# ASBB_Sonar.net
KiCad netlist of a schematic drawn in Altium Designer
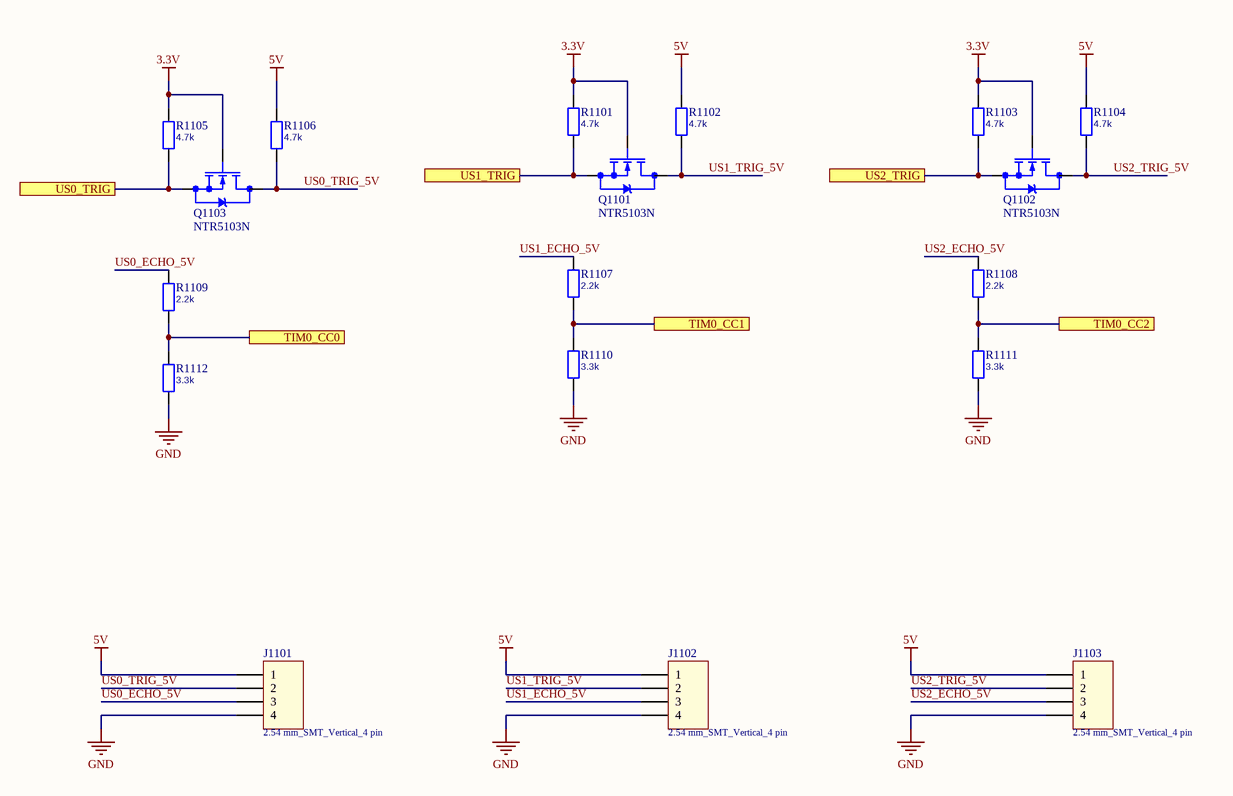
[diagram p0: ASBB_Sonar.SchDoc]

(export (version "E")
  (design (tool "Eeschema 10.0.6"))
  (components
    (comp (ref "J1101")
      (value "2.54 mm_SMT_Vertical_4 pin")
      (footprint "61000411921")
      (description "Socket Header WR-PHD, Pitch 2.54 mm, SMT, Vertical, single row, 4 pin")
      (fields (field (name "PART NUMBER") "61000411921") (field (name "PUBLISHER") "Wurth Elektronik"))
      (libsource (lib "6220xx21821 (rev18a)") (part "61000411921"))
    )
    (comp (ref "J1102")
      (value "2.54 mm_SMT_Vertical_4 pin")
      (footprint "61000411921")
      (description "Socket Header WR-PHD, Pitch 2.54 mm, SMT, Vertical, single row, 4 pin")
      (fields (field (name "PART NUMBER") "61000411921") (field (name "PUBLISHER") "Wurth Elektronik"))
      (libsource (lib "6220xx21821 (rev18a)") (part "61000411921"))
    )
    (comp (ref "J1103")
      (value "2.54 mm_SMT_Vertical_4 pin")
      (footprint "61000411921")
      (description "Socket Header WR-PHD, Pitch 2.54 mm, SMT, Vertical, single row, 4 pin")
      (fields (field (name "PART NUMBER") "61000411921") (field (name "PUBLISHER") "Wurth Elektronik"))
      (libsource (lib "6220xx21821 (rev18a)") (part "61000411921"))
    )
    (comp (ref "Q1101")
      (value "NTR5103N")
      (footprint "FZI:SOT23")
      (description "N-Channel MOSFET SOT23")
      (fields (field (name "PARTNUMBER") "?"))
      (libsource (lib "FZI") (part "NMOS SOT23"))
    )
    (comp (ref "Q1102")
      (value "NTR5103N")
      (footprint "FZI:SOT23")
      (description "N-Channel MOSFET SOT23")
      (fields (field (name "PARTNUMBER") "?"))
      (libsource (lib "FZI") (part "NMOS SOT23"))
    )
    (comp (ref "Q1103")
      (value "NTR5103N")
      (footprint "FZI:SOT23")
      (description "N-Channel MOSFET SOT23")
      (fields (field (name "PARTNUMBER") "?"))
      (libsource (lib "FZI") (part "NMOS SOT23"))
    )
    (comp (ref "R1101")
      (value "4.7k")
      (footprint "0603")
      (description "Resistor")
      (fields (field (name "PARTNUMBER") "?"))
      (libsource (lib "FZI") (part "Resistor"))
    )
    (comp (ref "R1102")
      (value "4.7k")
      (footprint "0603")
      (description "Resistor")
      (fields (field (name "PARTNUMBER") "?"))
      (libsource (lib "FZI") (part "Resistor"))
    )
    (comp (ref "R1103")
      (value "4.7k")
      (footprint "0603")
      (description "Resistor")
      (fields (field (name "PARTNUMBER") "?"))
      (libsource (lib "FZI") (part "Resistor"))
    )
    (comp (ref "R1104")
      (value "4.7k")
      (footprint "0603")
      (description "Resistor")
      (fields (field (name "PARTNUMBER") "?"))
      (libsource (lib "FZI") (part "Resistor"))
    )
    (comp (ref "R1105")
      (value "4.7k")
      (footprint "0603")
      (description "Resistor")
      (fields (field (name "PARTNUMBER") "?"))
      (libsource (lib "FZI") (part "Resistor"))
    )
    (comp (ref "R1106")
      (value "4.7k")
      (footprint "0603")
      (description "Resistor")
      (fields (field (name "PARTNUMBER") "?"))
      (libsource (lib "FZI") (part "Resistor"))
    )
    (comp (ref "R1107")
      (value "2.2k")
      (footprint "0603")
      (description "Resistor")
      (fields (field (name "PARTNUMBER") "?"))
      (libsource (lib "FZI") (part "Resistor"))
    )
    (comp (ref "R1108")
      (value "2.2k")
      (footprint "0603")
      (description "Resistor")
      (fields (field (name "PARTNUMBER") "?"))
      (libsource (lib "FZI") (part "Resistor"))
    )
    (comp (ref "R1109")
      (value "2.2k")
      (footprint "0603")
      (description "Resistor")
      (fields (field (name "PARTNUMBER") "?"))
      (libsource (lib "FZI") (part "Resistor"))
    )
    (comp (ref "R1110")
      (value "3.3k")
      (footprint "0603")
      (description "Resistor")
      (fields (field (name "PARTNUMBER") "?"))
      (libsource (lib "FZI") (part "Resistor"))
    )
    (comp (ref "R1111")
      (value "3.3k")
      (footprint "0603")
      (description "Resistor")
      (fields (field (name "PARTNUMBER") "?"))
      (libsource (lib "FZI") (part "Resistor"))
    )
    (comp (ref "R1112")
      (value "3.3k")
      (footprint "0603")
      (description "Resistor")
      (fields (field (name "PARTNUMBER") "?"))
      (libsource (lib "FZI") (part "Resistor"))
    )
  )
  (nets
    (net (code "1") (name "/TIM0_CC0") (class "Default")
      (node (ref "R1109") (pin "1") (pinfunction "1_1") (pintype "passive"))
      (node (ref "R1112") (pin "2") (pinfunction "2_2") (pintype "passive"))
    )
    (net (code "2") (name "/TIM0_CC1") (class "Default")
      (node (ref "R1107") (pin "1") (pinfunction "1_1") (pintype "passive"))
      (node (ref "R1110") (pin "2") (pinfunction "2_2") (pintype "passive"))
    )
    (net (code "3") (name "/TIM0_CC2") (class "Default")
      (node (ref "R1108") (pin "1") (pinfunction "1_1") (pintype "passive"))
      (node (ref "R1111") (pin "2") (pinfunction "2_2") (pintype "passive"))
    )
    (net (code "4") (name "/US0_ECHO_5V") (class "Default")
      (node (ref "J1101") (pin "3") (pinfunction "3_3") (pintype "passive"))
      (node (ref "R1109") (pin "2") (pinfunction "2_2") (pintype "passive"))
    )
    (net (code "5") (name "/US0_TRIG") (class "Default")
      (node (ref "Q1103") (pin "2") (pinfunction "S_2") (pintype "passive"))
      (node (ref "R1105") (pin "1") (pinfunction "1_1") (pintype "passive"))
    )
    (net (code "6") (name "/US0_TRIG_5V") (class "Default")
      (node (ref "J1101") (pin "2") (pinfunction "2_2") (pintype "passive"))
      (node (ref "Q1103") (pin "3") (pinfunction "D_3") (pintype "passive"))
      (node (ref "R1106") (pin "1") (pinfunction "1_1") (pintype "passive"))
    )
    (net (code "7") (name "/US1_ECHO_5V") (class "Default")
      (node (ref "J1102") (pin "3") (pinfunction "3_3") (pintype "passive"))
      (node (ref "R1107") (pin "2") (pinfunction "2_2") (pintype "passive"))
    )
    (net (code "8") (name "/US1_TRIG") (class "Default")
      (node (ref "Q1101") (pin "2") (pinfunction "S_2") (pintype "passive"))
      (node (ref "R1101") (pin "1") (pinfunction "1_1") (pintype "passive"))
    )
    (net (code "9") (name "/US1_TRIG_5V") (class "Default")
      (node (ref "J1102") (pin "2") (pinfunction "2_2") (pintype "passive"))
      (node (ref "Q1101") (pin "3") (pinfunction "D_3") (pintype "passive"))
      (node (ref "R1102") (pin "1") (pinfunction "1_1") (pintype "passive"))
    )
    (net (code "10") (name "/US2_ECHO_5V") (class "Default")
      (node (ref "J1103") (pin "3") (pinfunction "3_3") (pintype "passive"))
      (node (ref "R1108") (pin "2") (pinfunction "2_2") (pintype "passive"))
    )
    (net (code "11") (name "/US2_TRIG") (class "Default")
      (node (ref "Q1102") (pin "2") (pinfunction "S_2") (pintype "passive"))
      (node (ref "R1103") (pin "1") (pinfunction "1_1") (pintype "passive"))
    )
    (net (code "12") (name "/US2_TRIG_5V") (class "Default")
      (node (ref "J1103") (pin "2") (pinfunction "2_2") (pintype "passive"))
      (node (ref "Q1102") (pin "3") (pinfunction "D_3") (pintype "passive"))
      (node (ref "R1104") (pin "1") (pinfunction "1_1") (pintype "passive"))
    )
    (net (code "13") (name "3.3V") (class "Default")
      (node (ref "Q1101") (pin "1") (pinfunction "G_1") (pintype "passive"))
      (node (ref "Q1102") (pin "1") (pinfunction "G_1") (pintype "passive"))
      (node (ref "Q1103") (pin "1") (pinfunction "G_1") (pintype "passive"))
      (node (ref "R1101") (pin "2") (pinfunction "2_2") (pintype "passive"))
      (node (ref "R1103") (pin "2") (pinfunction "2_2") (pintype "passive"))
      (node (ref "R1105") (pin "2") (pinfunction "2_2") (pintype "passive"))
    )
    (net (code "14") (name "5V") (class "Default")
      (node (ref "J1101") (pin "1") (pinfunction "1_1") (pintype "passive"))
      (node (ref "J1102") (pin "1") (pinfunction "1_1") (pintype "passive"))
      (node (ref "J1103") (pin "1") (pinfunction "1_1") (pintype "passive"))
      (node (ref "R1102") (pin "2") (pinfunction "2_2") (pintype "passive"))
      (node (ref "R1104") (pin "2") (pinfunction "2_2") (pintype "passive"))
      (node (ref "R1106") (pin "2") (pinfunction "2_2") (pintype "passive"))
    )
    (net (code "15") (name "GND") (class "Default")
      (node (ref "J1101") (pin "4") (pinfunction "4_4") (pintype "passive"))
      (node (ref "J1102") (pin "4") (pinfunction "4_4") (pintype "passive"))
      (node (ref "J1103") (pin "4") (pinfunction "4_4") (pintype "passive"))
      (node (ref "R1110") (pin "1") (pinfunction "1_1") (pintype "passive"))
      (node (ref "R1111") (pin "1") (pinfunction "1_1") (pintype "passive"))
      (node (ref "R1112") (pin "1") (pinfunction "1_1") (pintype "passive"))
    )
  )
)
